# placaSinalizadores.net
KiCad netlist of a schematic drawn in EAGLE
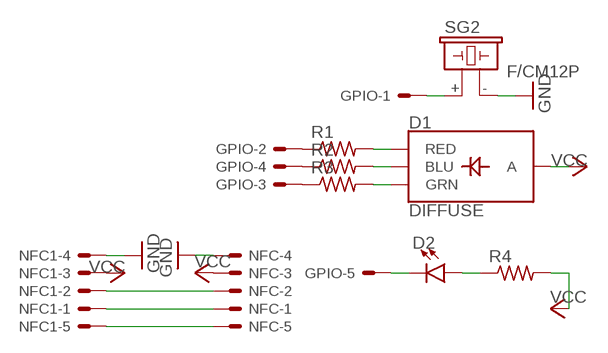
[diagram p0: schematic, sheet 1]

(export (version "E")
  (design (tool "Eeschema 10.0.6"))
  (components
    (comp (ref "D1")
      (value "DIFFUSE")
      (footprint "eagle-import:LED-RGB-THRU")
      (libsource (lib "eagle-import") (part "LED-RGB-CADIFFUSE"))
    )
    (comp (ref "D2")
      (value "LED5MM")
      (footprint "eagle-import:LED_5MM")
      (libsource (lib "eagle-import") (part "LED5MM"))
    )
    (comp (ref "GPIO")
      (value "JST-XH-05-PIN-LONG-PAD")
      (footprint "eagle-import:JST-XH-05-PACKAGE-LONG-PAD")
      (libsource (lib "eagle-import") (part "JST-XH-05-PIN-LONG-PAD"))
    )
    (comp (ref "NFC")
      (value "JST-XH-05-PIN-LONG-PAD")
      (footprint "eagle-import:JST-XH-05-PACKAGE-LONG-PAD")
      (libsource (lib "eagle-import") (part "JST-XH-05-PIN-LONG-PAD"))
    )
    (comp (ref "NFC1")
      (value "JST-XH-05-PIN-LONG-PAD")
      (footprint "eagle-import:JST-XH-05-PACKAGE-LONG-PAD")
      (libsource (lib "eagle-import") (part "JST-XH-05-PIN-LONG-PAD"))
    )
    (comp (ref "R1")
      (value "R-US_0204/7")
      (footprint "eagle-import:0204_7")
      (libsource (lib "eagle-import") (part "R-US_0204/7"))
    )
    (comp (ref "R2")
      (value "R-US_0204/7")
      (footprint "eagle-import:0204_7")
      (libsource (lib "eagle-import") (part "R-US_0204/7"))
    )
    (comp (ref "R3")
      (value "R-US_0204/7")
      (footprint "eagle-import:0204_7")
      (libsource (lib "eagle-import") (part "R-US_0204/7"))
    )
    (comp (ref "R4")
      (value "R-US_0204/7")
      (footprint "eagle-import:0204_7")
      (libsource (lib "eagle-import") (part "R-US_0204/7"))
    )
    (comp (ref "SG2")
      (value "F/CM12P")
      (footprint "eagle-import:F_CM12P")
      (libsource (lib "eagle-import") (part "F/CM12P"))
    )
  )
  (nets
    (net (code "1") (name "GND") (class "Default")
      (node (ref "NFC") (pin "4") (pinfunction "S_4") (pintype "passive"))
      (node (ref "NFC1") (pin "4") (pinfunction "S_4") (pintype "passive"))
      (node (ref "SG2") (pin "-") (pinfunction "2_-") (pintype "passive"))
    )
    (net (code "2") (name "Net-(D1-BLU)") (class "Default")
      (node (ref "D1") (pin "4") (pinfunction "BLU_4") (pintype "bidirectional"))
      (node (ref "R2") (pin "2") (pinfunction "2_2") (pintype "passive"))
    )
    (net (code "3") (name "Net-(D1-GRN)") (class "Default")
      (node (ref "D1") (pin "3") (pinfunction "GRN_3") (pintype "bidirectional"))
      (node (ref "R3") (pin "2") (pinfunction "2_2") (pintype "passive"))
    )
    (net (code "4") (name "Net-(D1-RED)") (class "Default")
      (node (ref "D1") (pin "1") (pinfunction "RED_1") (pintype "bidirectional"))
      (node (ref "R1") (pin "2") (pinfunction "2_2") (pintype "passive"))
    )
    (net (code "5") (name "Net-(D2-C)") (class "Default")
      (node (ref "D2") (pin "K") (pinfunction "C_K") (pintype "passive"))
      (node (ref "GPIO") (pin "5") (pinfunction "S_5") (pintype "passive"))
    )
    (net (code "6") (name "Net-(D2-PadA)") (class "Default")
      (node (ref "D2") (pin "A") (pinfunction "A_A") (pintype "passive"))
      (node (ref "R4") (pin "1") (pinfunction "1_1") (pintype "passive"))
    )
    (net (code "7") (name "Net-(GPIOA-S)") (class "Default")
      (node (ref "GPIO") (pin "1") (pinfunction "S_1") (pintype "passive"))
      (node (ref "SG2") (pin "+") (pinfunction "1_+") (pintype "passive"))
    )
    (net (code "8") (name "Net-(GPIOB-S)") (class "Default")
      (node (ref "GPIO") (pin "2") (pinfunction "S_2") (pintype "passive"))
      (node (ref "R1") (pin "1") (pinfunction "1_1") (pintype "passive"))
    )
    (net (code "9") (name "Net-(GPIOC-S)") (class "Default")
      (node (ref "GPIO") (pin "3") (pinfunction "S_3") (pintype "passive"))
      (node (ref "R3") (pin "1") (pinfunction "1_1") (pintype "passive"))
    )
    (net (code "10") (name "Net-(GPIOD-S)") (class "Default")
      (node (ref "GPIO") (pin "4") (pinfunction "S_4") (pintype "passive"))
      (node (ref "R2") (pin "1") (pinfunction "1_1") (pintype "passive"))
    )
    (net (code "11") (name "Net-(NFC1A-S)") (class "Default")
      (node (ref "NFC") (pin "1") (pinfunction "S_1") (pintype "passive"))
      (node (ref "NFC1") (pin "1") (pinfunction "S_1") (pintype "passive"))
    )
    (net (code "12") (name "Net-(NFC1B-S)") (class "Default")
      (node (ref "NFC") (pin "2") (pinfunction "S_2") (pintype "passive"))
      (node (ref "NFC1") (pin "2") (pinfunction "S_2") (pintype "passive"))
    )
    (net (code "13") (name "Net-(NFC1E-S)") (class "Default")
      (node (ref "NFC") (pin "5") (pinfunction "S_5") (pintype "passive"))
      (node (ref "NFC1") (pin "5") (pinfunction "S_5") (pintype "passive"))
    )
    (net (code "14") (name "VCC") (class "Default")
      (node (ref "D1") (pin "2") (pinfunction "A_2") (pintype "bidirectional"))
      (node (ref "NFC") (pin "3") (pinfunction "S_3") (pintype "passive"))
      (node (ref "NFC1") (pin "3") (pinfunction "S_3") (pintype "passive"))
      (node (ref "R4") (pin "2") (pinfunction "2_2") (pintype "passive"))
    )
  )
)
